# POWER_2.net
KiCad netlist of a schematic drawn in Altium Designer
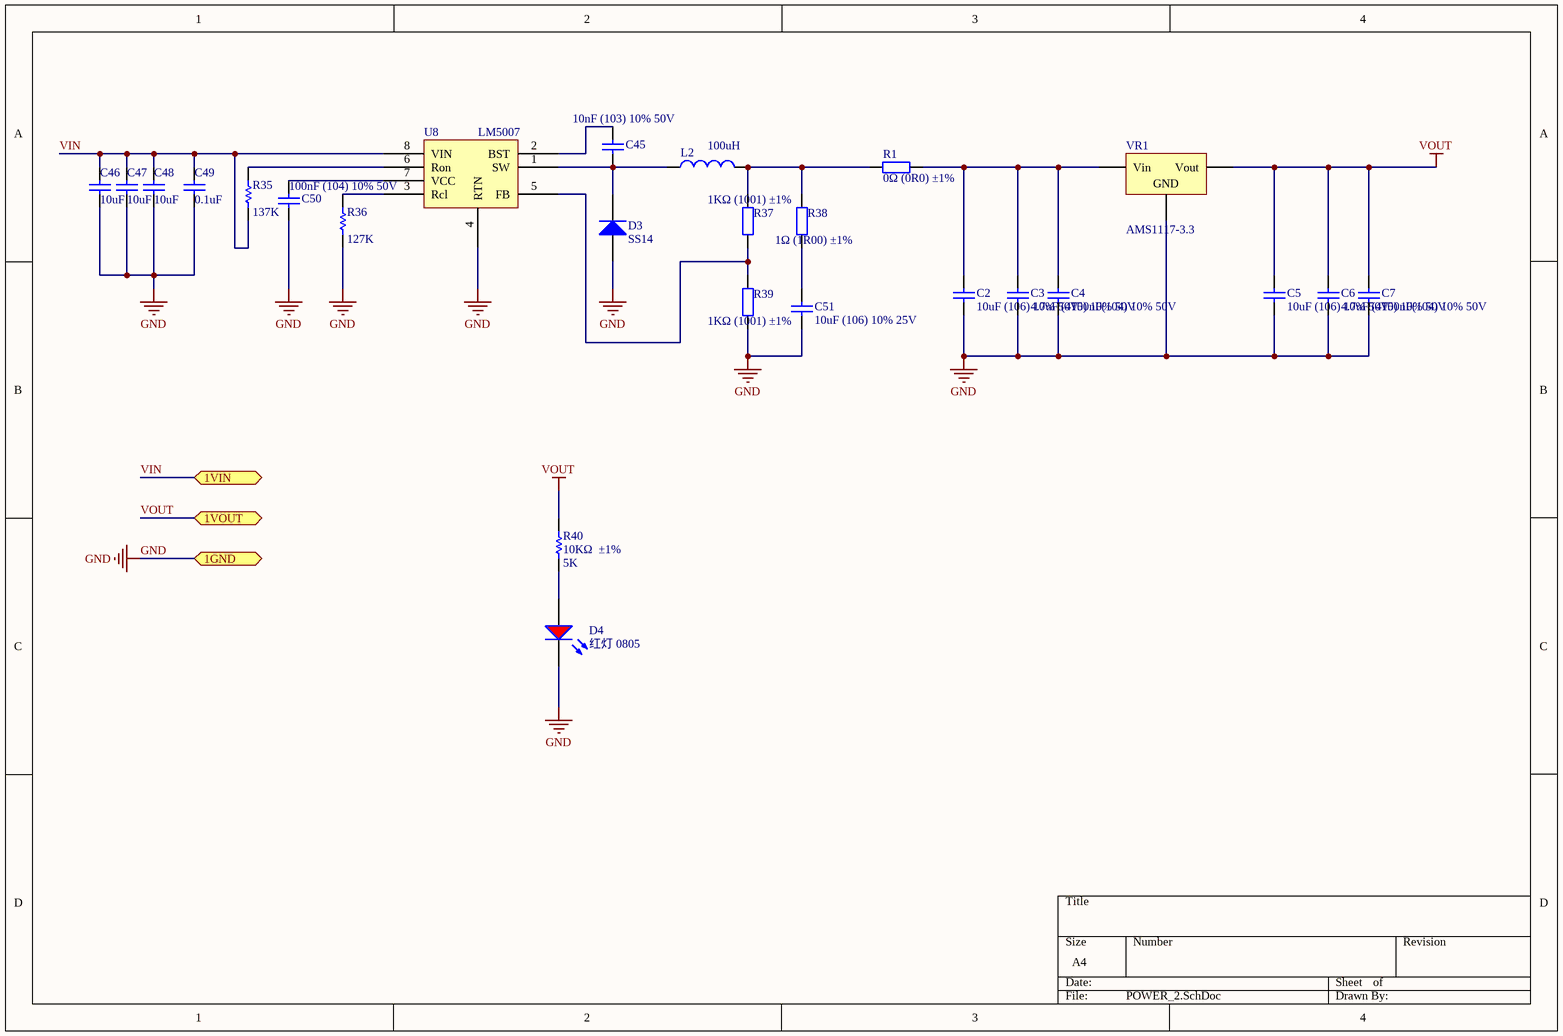
[diagram p0: POWER_2.SchDoc]

(export (version "E")
  (design (tool "Eeschema 10.0.6"))
  (components
    (comp (ref "C2")
      (value "10uF (106) 10% 50V")
      (footprint "1206_C")
      (description "贴片电容")
      (libsource (lib "Cap") (part "1206 10uF (106) 10% 50V"))
    )
    (comp (ref "C3")
      (value "4.7uF (475) 10% 50V")
      (footprint "1206_C")
      (description "贴片电容")
      (libsource (lib "Cap") (part "1206 4.7uF (475) 10% 50V"))
    )
    (comp (ref "C4")
      (value "100nF(104) 10% 50V")
      (footprint "0805_C")
      (description "贴片电容")
      (libsource (lib "Cap") (part "0805 100nF(104) 10% 50V"))
    )
    (comp (ref "C5")
      (value "10uF (106) 10% 50V")
      (footprint "1206_C")
      (description "贴片电容")
      (libsource (lib "Cap") (part "1206 10uF (106) 10% 50V"))
    )
    (comp (ref "C6")
      (value "4.7uF (475) 10% 50V")
      (footprint "1206_C")
      (description "贴片电容")
      (libsource (lib "Cap") (part "1206 4.7uF (475) 10% 50V"))
    )
    (comp (ref "C7")
      (value "100nF(104) 10% 50V")
      (footprint "0805_C")
      (description "贴片电容")
      (libsource (lib "Cap") (part "0805 100nF(104) 10% 50V"))
    )
    (comp (ref "C45")
      (value "10nF (103) 10% 50V")
      (footprint "1206_C")
      (description "贴片电容")
      (libsource (lib "Miscellaneous Devices LC") (part "1206 10nF (103) 10% 50V"))
    )
    (comp (ref "C46")
      (value "10uF")
      (footprint "C1206")
      (description "Capacitor")
      (fields (field (name "Comment") "10uF (106) ±10% 50V") (field (name "PUBLISHER") "Altium Limited"))
      (libsource (lib "Miscellaneous Devices") (part "Cap"))
    )
    (comp (ref "C47")
      (value "10uF")
      (footprint "C1206")
      (description "Capacitor")
      (fields (field (name "Comment") "10uF (106) ±10% 50V") (field (name "PUBLISHER") "Altium Limited"))
      (libsource (lib "Miscellaneous Devices") (part "Cap"))
    )
    (comp (ref "C48")
      (value "10uF")
      (footprint "C1206")
      (description "Capacitor")
      (fields (field (name "Comment") "10uF (106) ±10% 50V") (field (name "PUBLISHER") "Altium Limited"))
      (libsource (lib "Miscellaneous Devices") (part "Cap"))
    )
    (comp (ref "C49")
      (value "0.1uF")
      (footprint "1608[0603]")
      (description "Capacitor")
      (fields (field (name "Comment") "100nF (104) ±10% 50V") (field (name "PUBLISHER") "Altium Limited"))
      (libsource (lib "Miscellaneous Devices") (part "Cap"))
    )
    (comp (ref "C50")
      (value "100nF (104) 10% 50V")
      (footprint "1206_C")
      (description "贴片电容")
      (libsource (lib "Miscellaneous Devices LC") (part "1206 100nF (104) 10% 50V"))
    )
    (comp (ref "C51")
      (value "10uF (106) 10% 25V")
      (footprint "0805_C")
      (description "贴片电容")
      (libsource (lib "Miscellaneous Devices LC") (part "0805 10uF (106) 10% 25V"))
    )
    (comp (ref "D3")
      (value "SS14")
      (footprint "SS14")
      (description "Default Diode")
      (fields (field (name "PUBLISHER") "Altium Limited"))
      (libsource (lib "Miscellaneous Devices") (part "Diode"))
    )
    (comp (ref "D4")
      (value "红灯 0805")
      (footprint "0805_LED_S1")
      (description "发光二极管")
      (libsource (lib "Miscellaneous Devices LC") (part "0805 红灯"))
    )
    (comp (ref "L2")
      (value "100uH")
      (footprint "Inductance220UH")
      (description "Inductor")
      (fields (field (name "PUBLISHER") "Altium Limited"))
      (libsource (lib "Miscellaneous Devices") (part "Inductor"))
    )
    (comp (ref "R1")
      (value "0Ω (0R0) ±1%")
      (footprint "1206_R")
      (description "贴片电阻")
      (libsource (lib "RES") (part "1206 0Ω (0R0) 1%"))
    )
    (comp (ref "R35")
      (value "137K")
      (footprint "0805_R")
      (description "Resistor")
      (fields (field (name "Comment") "137KΩ  ±1%") (field (name "PUBLISHER") "Altium Limited"))
      (libsource (lib "Miscellaneous Devices") (part "Res1"))
    )
    (comp (ref "R36")
      (value "127K")
      (footprint "0805_R")
      (description "Resistor")
      (fields (field (name "Comment") "127KΩ (1003) ±1%") (field (name "PUBLISHER") "Altium Limited"))
      (libsource (lib "Miscellaneous Devices") (part "Res1"))
    )
    (comp (ref "R37")
      (value "1KΩ (1001) ±1%")
      (footprint "0805_R")
      (description "贴片电阻")
      (libsource (lib "Miscellaneous Devices LC") (part "0805 1KΩ (1001) 1%"))
    )
    (comp (ref "R38")
      (value "1Ω (1R00) ±1%")
      (footprint "0805_R")
      (description "贴片电阻")
      (libsource (lib "Miscellaneous Devices LC") (part "0805 1Ω (1R00) 1%"))
    )
    (comp (ref "R39")
      (value "1KΩ (1001) ±1%")
      (footprint "0805_R")
      (description "贴片电阻")
      (libsource (lib "Miscellaneous Devices LC") (part "0805 1KΩ (1001) 1%"))
    )
    (comp (ref "R40")
      (value "10KΩ  ±1%")
      (footprint "0805_R")
      (description "Resistor")
      (fields (field (name "ALTIUM_VALUE") "5K") (field (name "PUBLISHER") "Altium Limited"))
      (libsource (lib "Miscellaneous Devices") (part "Res1"))
    )
    (comp (ref "U8") (value "LM5007") (footprint "LM5007") (libsource (lib "LS_Schlib1") (part "LM5007")))
    (comp (ref "VR1")
      (value "AMS1117-3.3")
      (footprint "SOT-223")
      (description "低压差线性稳压(LDO)")
      (libsource (lib "LDO") (part "SOT-223 AMS1117-3.3"))
    )
  )
  (nets
    (net (code "1") (name "/VIN") (class "Default")
      (node (ref "C46") (pin "2") (pinfunction "2_2") (pintype "passive"))
      (node (ref "C47") (pin "2") (pinfunction "2_2") (pintype "passive"))
      (node (ref "C48") (pin "2") (pinfunction "2_2") (pintype "passive"))
      (node (ref "C49") (pin "2") (pinfunction "2_2") (pintype "passive"))
      (node (ref "R35") (pin "1") (pinfunction "1_1") (pintype "passive"))
      (node (ref "U8") (pin "8") (pinfunction "VIN_8") (pintype "passive"))
    )
    (net (code "2") (name "GND") (class "Default")
      (node (ref "C2") (pin "1") (pinfunction "1_1") (pintype "passive"))
      (node (ref "C3") (pin "1") (pinfunction "1_1") (pintype "passive"))
      (node (ref "C4") (pin "1") (pinfunction "1_1") (pintype "passive"))
      (node (ref "C46") (pin "1") (pinfunction "1_1") (pintype "passive"))
      (node (ref "C47") (pin "1") (pinfunction "1_1") (pintype "passive"))
      (node (ref "C48") (pin "1") (pinfunction "1_1") (pintype "passive"))
      (node (ref "C49") (pin "1") (pinfunction "1_1") (pintype "passive"))
      (node (ref "C5") (pin "1") (pinfunction "1_1") (pintype "passive"))
      (node (ref "C50") (pin "1") (pinfunction "1_1") (pintype "passive"))
      (node (ref "C51") (pin "1") (pinfunction "1_1") (pintype "passive"))
      (node (ref "C6") (pin "1") (pinfunction "1_1") (pintype "passive"))
      (node (ref "C7") (pin "1") (pinfunction "1_1") (pintype "passive"))
      (node (ref "D3") (pin "1") (pinfunction "A_1") (pintype "passive"))
      (node (ref "D4") (pin "K") (pinfunction "K_K") (pintype "passive"))
      (node (ref "R36") (pin "1") (pinfunction "1_1") (pintype "passive"))
      (node (ref "R39") (pin "1") (pinfunction "1_1") (pintype "passive"))
      (node (ref "U8") (pin "4") (pinfunction "RTN_4") (pintype "passive"))
      (node (ref "VR1") (pin "1") (pinfunction "GND_1") (pintype "passive"))
    )
    (net (code "3") (name "Net-(C51-Pad2)") (class "Default")
      (node (ref "C51") (pin "2") (pinfunction "2_2") (pintype "passive"))
      (node (ref "R38") (pin "1") (pinfunction "1_1") (pintype "passive"))
    )
    (net (code "4") (name "Net-(D3-K)") (class "Default")
      (node (ref "C45") (pin "1") (pinfunction "1_1") (pintype "passive"))
      (node (ref "D3") (pin "2") (pinfunction "K_2") (pintype "passive"))
      (node (ref "L2") (pin "1") (pinfunction "1_1") (pintype "passive"))
      (node (ref "U8") (pin "1") (pinfunction "SW_1") (pintype "passive"))
    )
    (net (code "5") (name "Net-(D4-PadA)") (class "Default")
      (node (ref "D4") (pin "A") (pinfunction "A_A") (pintype "passive"))
      (node (ref "R40") (pin "1") (pinfunction "1_1") (pintype "passive"))
    )
    (net (code "6") (name "Net-(L2-Pad2)") (class "Default")
      (node (ref "L2") (pin "2") (pinfunction "2_2") (pintype "passive"))
      (node (ref "R1") (pin "1") (pinfunction "1_1") (pintype "passive"))
      (node (ref "R37") (pin "2") (pinfunction "2_2") (pintype "passive"))
      (node (ref "R38") (pin "2") (pinfunction "2_2") (pintype "passive"))
    )
    (net (code "7") (name "Net-(U8-BST)") (class "Default")
      (node (ref "C45") (pin "2") (pinfunction "2_2") (pintype "passive"))
      (node (ref "U8") (pin "2") (pinfunction "BST_2") (pintype "passive"))
    )
    (net (code "8") (name "Net-(U8-FB)") (class "Default")
      (node (ref "R37") (pin "1") (pinfunction "1_1") (pintype "passive"))
      (node (ref "R39") (pin "2") (pinfunction "2_2") (pintype "passive"))
      (node (ref "U8") (pin "5") (pinfunction "FB_5") (pintype "passive"))
    )
    (net (code "9") (name "Net-(U8-Rcl)") (class "Default")
      (node (ref "R36") (pin "2") (pinfunction "2_2") (pintype "passive"))
      (node (ref "U8") (pin "3") (pinfunction "Rcl_3") (pintype "passive"))
    )
    (net (code "10") (name "Net-(U8-Ron)") (class "Default")
      (node (ref "R35") (pin "2") (pinfunction "2_2") (pintype "passive"))
      (node (ref "U8") (pin "6") (pinfunction "Ron_6") (pintype "passive"))
    )
    (net (code "11") (name "Net-(U8-VCC)") (class "Default")
      (node (ref "C50") (pin "2") (pinfunction "2_2") (pintype "passive"))
      (node (ref "U8") (pin "7") (pinfunction "VCC_7") (pintype "passive"))
    )
    (net (code "12") (name "Net-(VR1-Vin)") (class "Default")
      (node (ref "C2") (pin "2") (pinfunction "2_2") (pintype "passive"))
      (node (ref "C3") (pin "2") (pinfunction "2_2") (pintype "passive"))
      (node (ref "C4") (pin "2") (pinfunction "2_2") (pintype "passive"))
      (node (ref "R1") (pin "2") (pinfunction "2_2") (pintype "passive"))
      (node (ref "VR1") (pin "3") (pinfunction "Vin_3") (pintype "passive"))
    )
    (net (code "13") (name "VOUT") (class "Default")
      (node (ref "C5") (pin "2") (pinfunction "2_2") (pintype "passive"))
      (node (ref "C6") (pin "2") (pinfunction "2_2") (pintype "passive"))
      (node (ref "C7") (pin "2") (pinfunction "2_2") (pintype "passive"))
      (node (ref "R40") (pin "2") (pinfunction "2_2") (pintype "passive"))
      (node (ref "VR1") (pin "2") (pinfunction "Vout_2") (pintype "passive"))
    )
  )
)
